# 1_0.net
KiCad netlist of a schematic drawn in EAGLE
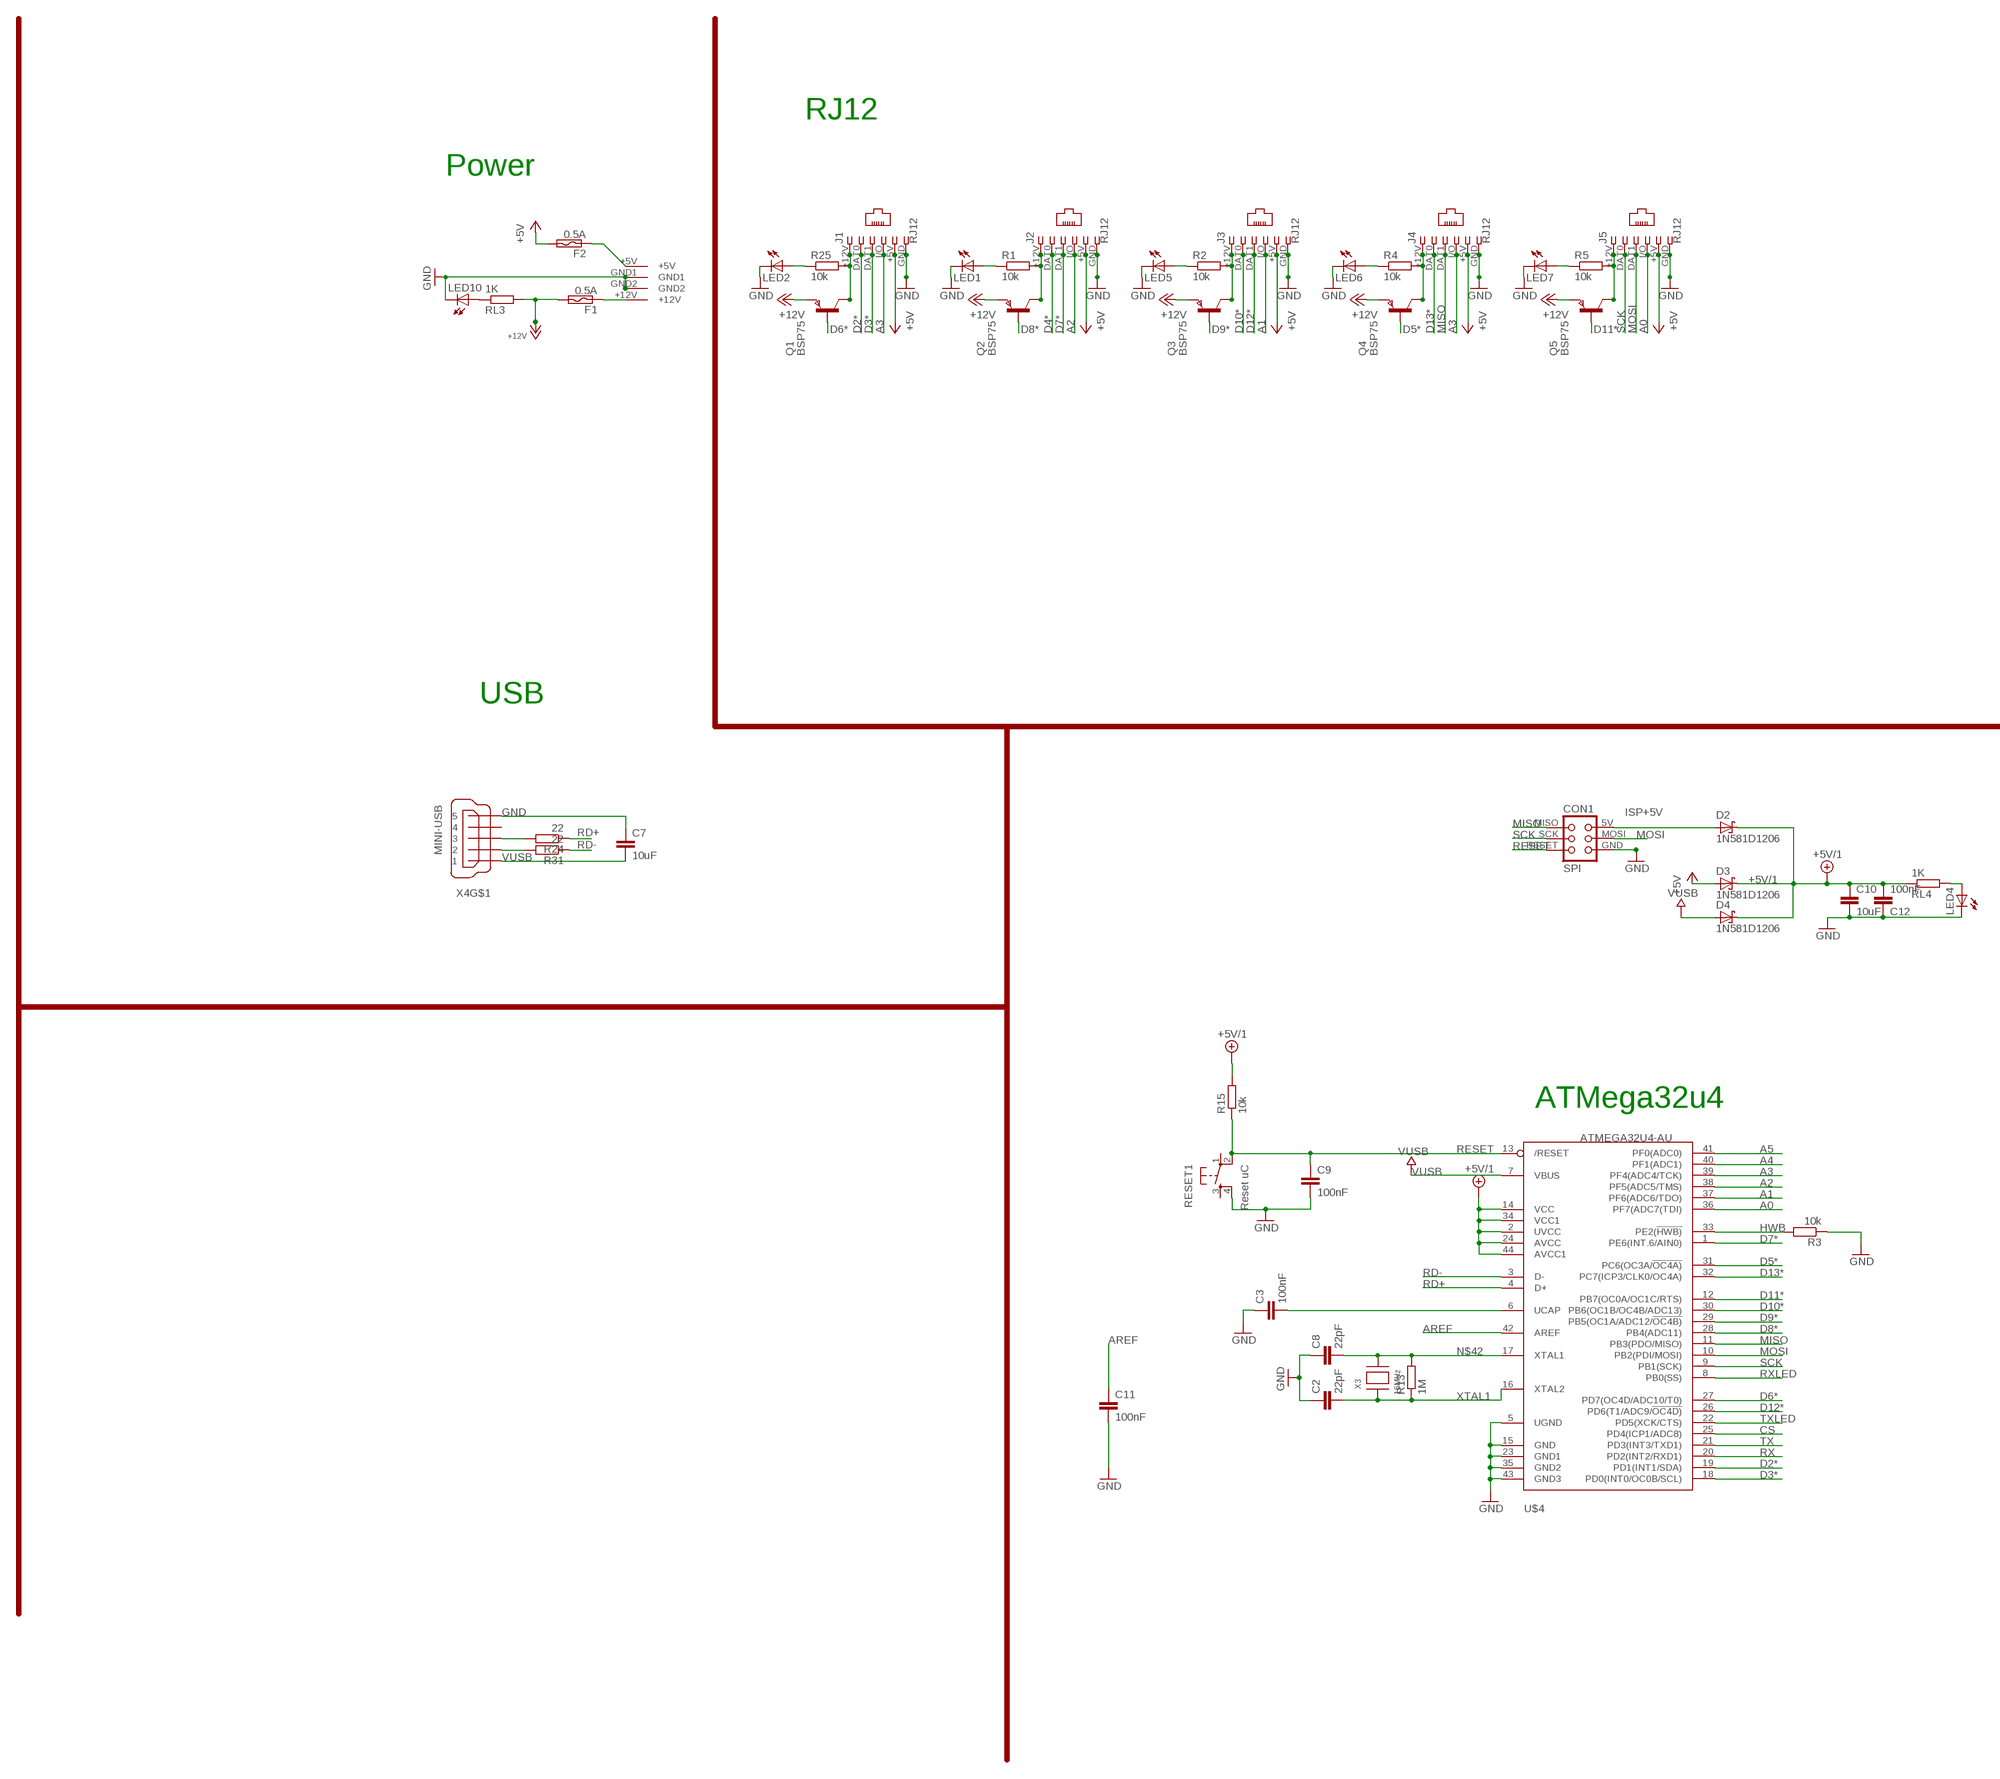
[diagram p0: schematic, sheet 1, part 1 of 2]
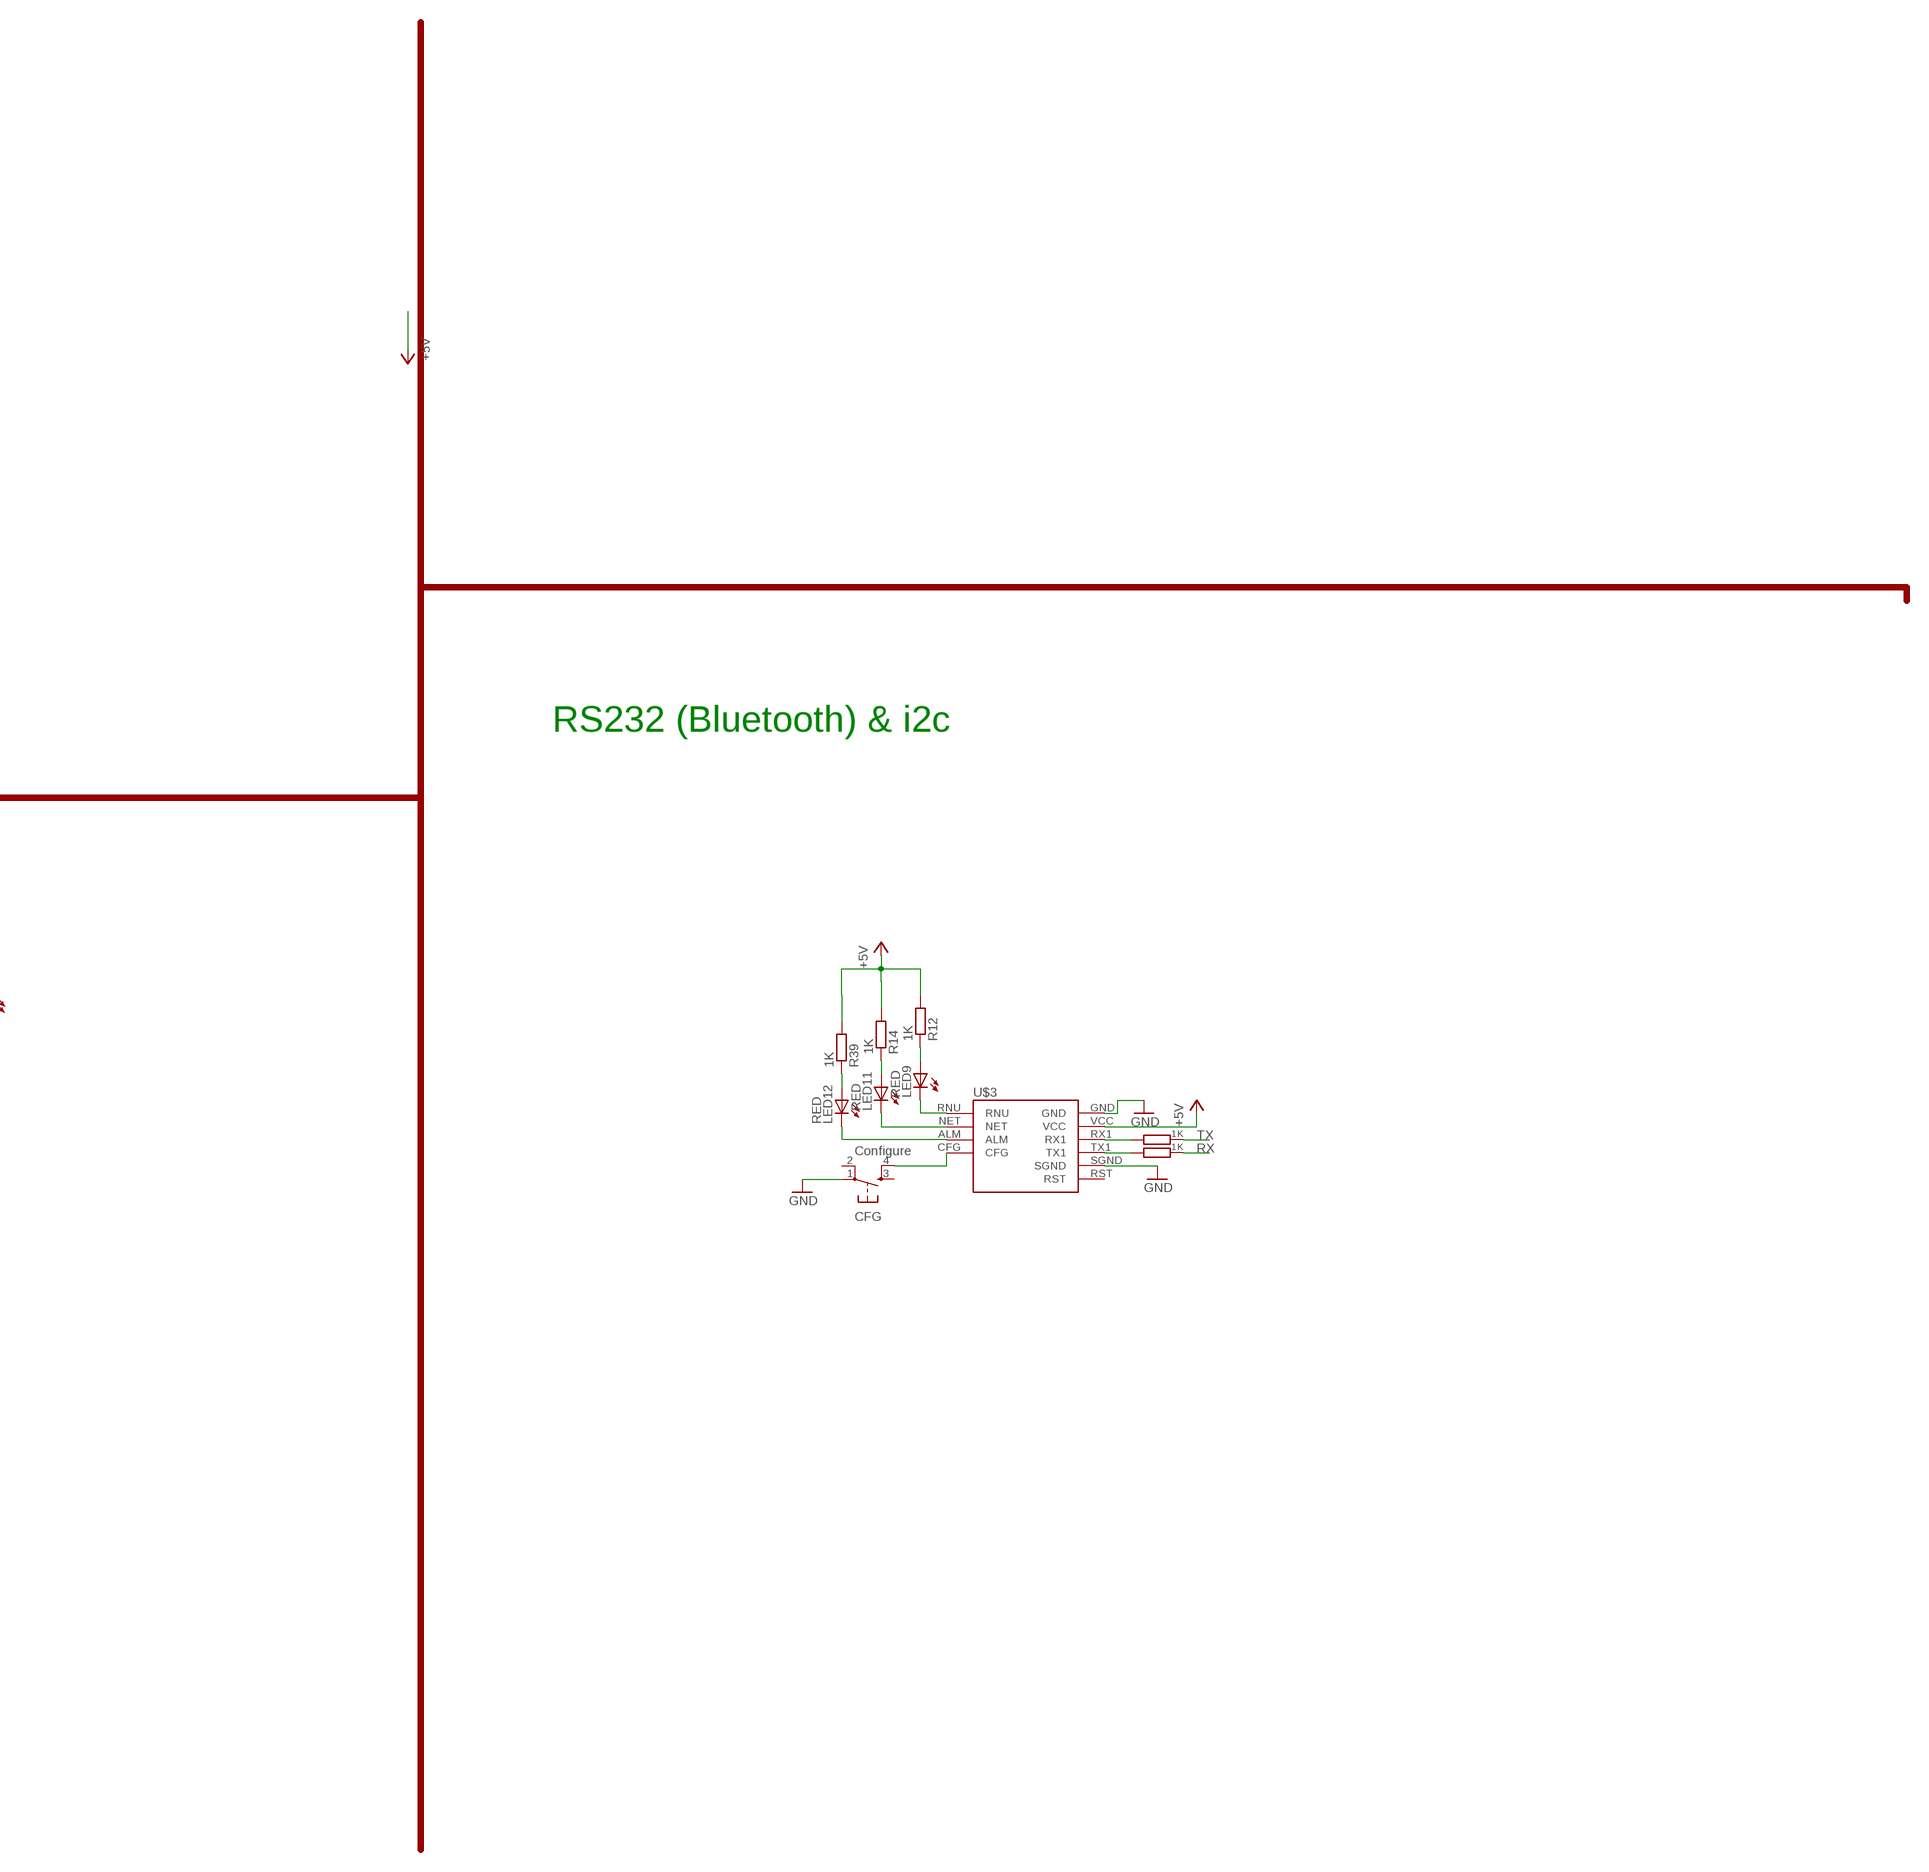
[diagram p1: schematic, sheet 1, part 2 of 2]

(export (version "E")
  (design (tool "Eeschema 10.0.6"))
  (components
    (comp (ref "C2")
      (value "22pF")
      (footprint "eagle-import:C1206")
      (libsource (lib "eagle-import") (part "C-EUC1206"))
    )
    (comp (ref "C3")
      (value "100nF")
      (footprint "eagle-import:C1206")
      (libsource (lib "eagle-import") (part "C-EUC1206"))
    )
    (comp (ref "C7")
      (value "10uF")
      (footprint "eagle-import:C1206")
      (libsource (lib "eagle-import") (part "C-EUC1206"))
    )
    (comp (ref "C8")
      (value "22pF")
      (footprint "eagle-import:C1206")
      (libsource (lib "eagle-import") (part "C-EUC1206"))
    )
    (comp (ref "C9")
      (value "100nF")
      (footprint "eagle-import:C1206")
      (libsource (lib "eagle-import") (part "C-EUC1206"))
    )
    (comp (ref "C10")
      (value "10uF")
      (footprint "eagle-import:C1206")
      (libsource (lib "eagle-import") (part "C-EUC1206"))
    )
    (comp (ref "C11")
      (value "100nF")
      (footprint "eagle-import:C1206")
      (libsource (lib "eagle-import") (part "C-EUC1206"))
    )
    (comp (ref "C12")
      (value "100nF")
      (footprint "eagle-import:C1206")
      (libsource (lib "eagle-import") (part "C-EUC1206"))
    )
    (comp (ref "CFG")
      (value "Configure")
      (footprint "eagle-import:TACTILE_SWITCH_SMD")
      (libsource (lib "eagle-import") (part "TAC_SWITCHSMD"))
    )
    (comp (ref "CON1")
      (value "SPI")
      (footprint "eagle-import:TC2030-MCP")
      (libsource (lib "eagle-import") (part "TINYISPTAG"))
    )
    (comp (ref "D2")
      (value "1N581D1206")
      (footprint "eagle-import:LED-1206")
      (libsource (lib "eagle-import") (part "1N581D1206"))
    )
    (comp (ref "D3")
      (value "1N581D1206")
      (footprint "eagle-import:LED-1206")
      (libsource (lib "eagle-import") (part "1N581D1206"))
    )
    (comp (ref "D4")
      (value "1N581D1206")
      (footprint "eagle-import:LED-1206")
      (libsource (lib "eagle-import") (part "1N581D1206"))
    )
    (comp (ref "F1")
      (value "0.5A")
      (footprint "eagle-import:C1812")
      (libsource (lib "eagle-import") (part "POLYSWITCHSMD1812"))
    )
    (comp (ref "F2")
      (value "0.5A")
      (footprint "eagle-import:C1812")
      (libsource (lib "eagle-import") (part "POLYSWITCHSMD1812"))
    )
    (comp (ref "J1")
      (value "RJ12")
      (footprint "eagle-import:RJ12-STRAIGHT-WIEGAND")
      (libsource (lib "eagle-import") (part "RJ12STR-WIEGAND"))
    )
    (comp (ref "J2")
      (value "RJ12")
      (footprint "eagle-import:RJ12-STRAIGHT-WIEGAND")
      (libsource (lib "eagle-import") (part "RJ12STR-WIEGAND"))
    )
    (comp (ref "J3")
      (value "RJ12")
      (footprint "eagle-import:RJ12-STRAIGHT-WIEGAND")
      (libsource (lib "eagle-import") (part "RJ12STR-WIEGAND"))
    )
    (comp (ref "J4")
      (value "RJ12")
      (footprint "eagle-import:RJ12-STRAIGHT-WIEGAND")
      (libsource (lib "eagle-import") (part "RJ12STR-WIEGAND"))
    )
    (comp (ref "J5")
      (value "RJ12")
      (footprint "eagle-import:RJ12-STRAIGHT-WIEGAND")
      (libsource (lib "eagle-import") (part "RJ12STR-WIEGAND"))
    )
    (comp (ref "LED1")
      (value "Blue")
      (footprint "eagle-import:LED3MM")
      (libsource (lib "eagle-import") (part "lpatiny_LED3MM"))
    )
    (comp (ref "LED2")
      (value "Blue")
      (footprint "eagle-import:LED3MM")
      (libsource (lib "eagle-import") (part "lpatiny_LED3MM"))
    )
    (comp (ref "LED4")
      (value "RED")
      (footprint "eagle-import:LED3MM")
      (libsource (lib "eagle-import") (part "lpatiny_LED3MM"))
    )
    (comp (ref "LED5")
      (value "Blue")
      (footprint "eagle-import:LED3MM")
      (libsource (lib "eagle-import") (part "lpatiny_LED3MM"))
    )
    (comp (ref "LED6")
      (value "Blue")
      (footprint "eagle-import:LED3MM")
      (libsource (lib "eagle-import") (part "lpatiny_LED3MM"))
    )
    (comp (ref "LED7")
      (value "Blue")
      (footprint "eagle-import:LED3MM")
      (libsource (lib "eagle-import") (part "lpatiny_LED3MM"))
    )
    (comp (ref "LED9")
      (value "RED")
      (footprint "eagle-import:CHIP-LED0805")
      (libsource (lib "eagle-import") (part "LEDCHIP-LED0805"))
    )
    (comp (ref "LED10")
      (value "RED")
      (footprint "eagle-import:LED3MM")
      (libsource (lib "eagle-import") (part "lpatiny_LED3MM"))
    )
    (comp (ref "LED11")
      (value "RED")
      (footprint "eagle-import:CHIP-LED0805")
      (libsource (lib "eagle-import") (part "LEDCHIP-LED0805"))
    )
    (comp (ref "LED12")
      (value "RED")
      (footprint "eagle-import:CHIP-LED0805")
      (libsource (lib "eagle-import") (part "LEDCHIP-LED0805"))
    )
    (comp (ref "Q1")
      (value "BSP75")
      (footprint "eagle-import:SOT223")
      (fields (field (name "MPN") "DJT4030P-13"))
      (libsource (lib "eagle-import") (part "PNPSOT223"))
    )
    (comp (ref "Q2")
      (value "BSP75")
      (footprint "eagle-import:SOT223")
      (fields (field (name "MPN") "DJT4030P-13"))
      (libsource (lib "eagle-import") (part "PNPSOT223"))
    )
    (comp (ref "Q3")
      (value "BSP75")
      (footprint "eagle-import:SOT223")
      (fields (field (name "MPN") "DJT4030P-13"))
      (libsource (lib "eagle-import") (part "PNPSOT223"))
    )
    (comp (ref "Q4")
      (value "BSP75")
      (footprint "eagle-import:SOT223")
      (fields (field (name "MPN") "DJT4030P-13"))
      (libsource (lib "eagle-import") (part "PNPSOT223"))
    )
    (comp (ref "Q5")
      (value "BSP75")
      (footprint "eagle-import:SOT223")
      (fields (field (name "MPN") "DJT4030P-13"))
      (libsource (lib "eagle-import") (part "PNPSOT223"))
    )
    (comp (ref "R1")
      (value "10k")
      (footprint "eagle-import:R0805")
      (libsource (lib "eagle-import") (part "R-EU_R0805"))
    )
    (comp (ref "R2")
      (value "10k")
      (footprint "eagle-import:R0805")
      (libsource (lib "eagle-import") (part "R-EU_R0805"))
    )
    (comp (ref "R3")
      (value "10k")
      (footprint "eagle-import:M0805")
      (libsource (lib "eagle-import") (part "resistor_R-EU_M0805"))
    )
    (comp (ref "R4")
      (value "10k")
      (footprint "eagle-import:R0805")
      (libsource (lib "eagle-import") (part "R-EU_R0805"))
    )
    (comp (ref "R5")
      (value "10k")
      (footprint "eagle-import:R0805")
      (libsource (lib "eagle-import") (part "R-EU_R0805"))
    )
    (comp (ref "R8")
      (value "1K")
      (footprint "eagle-import:R0805")
      (libsource (lib "eagle-import") (part "R-EU_R0805"))
    )
    (comp (ref "R11")
      (value "1K")
      (footprint "eagle-import:R0805")
      (libsource (lib "eagle-import") (part "R-EU_R0805"))
    )
    (comp (ref "R12")
      (value "1K")
      (footprint "eagle-import:R0805")
      (libsource (lib "eagle-import") (part "R-EU_R0805"))
    )
    (comp (ref "R13")
      (value "1M")
      (footprint "eagle-import:R1206")
      (libsource (lib "eagle-import") (part "R-EU_R1206"))
    )
    (comp (ref "R14")
      (value "1K")
      (footprint "eagle-import:R0805")
      (libsource (lib "eagle-import") (part "R-EU_R0805"))
    )
    (comp (ref "R15")
      (value "10k")
      (footprint "eagle-import:M0805")
      (libsource (lib "eagle-import") (part "resistor_R-EU_M0805"))
    )
    (comp (ref "R24")
      (value "22")
      (footprint "eagle-import:M1206")
      (libsource (lib "eagle-import") (part "resistor_R-EU_M1206"))
    )
    (comp (ref "R25")
      (value "10k")
      (footprint "eagle-import:R0805")
      (libsource (lib "eagle-import") (part "R-EU_R0805"))
    )
    (comp (ref "R31")
      (value "22")
      (footprint "eagle-import:M1206")
      (libsource (lib "eagle-import") (part "resistor_R-EU_M1206"))
    )
    (comp (ref "R39")
      (value "1K")
      (footprint "eagle-import:R0805")
      (libsource (lib "eagle-import") (part "R-EU_R0805"))
    )
    (comp (ref "RESET1")
      (value "Reset uC")
      (footprint "eagle-import:TACTILE_SWITCH_SMD")
      (libsource (lib "eagle-import") (part "TAC_SWITCHSMD"))
    )
    (comp (ref "RL3")
      (value "1K")
      (footprint "eagle-import:R0805")
      (libsource (lib "eagle-import") (part "R-EU_R0805"))
    )
    (comp (ref "RL4")
      (value "1K")
      (footprint "eagle-import:R0805")
      (libsource (lib "eagle-import") (part "resistor_R-EU_R0805"))
    )
    (comp (ref "U$3")
      (value "SZ05-ZIGBEE")
      (footprint "eagle-import:SZ05-ZIGBEE")
      (libsource (lib "eagle-import") (part "SZ05-ZIGBEE"))
    )
    (comp (ref "U$4")
      (value "ATMEGA32U4-AU")
      (footprint "eagle-import:TQFP44")
      (libsource (lib "eagle-import") (part "ATMEGA32U4-AU"))
    )
    (comp (ref "U$6")
      (value "KPJX-4S-S")
      (footprint "eagle-import:KPJX-4S-S")
      (libsource (lib "eagle-import") (part "KPJX-4S-S"))
    )
    (comp (ref "X3")
      (value "16MHz")
      (footprint "eagle-import:NX6035")
      (libsource (lib "eagle-import") (part "XTALNX6035"))
    )
    (comp (ref "X4")
      (value "MINI-USB")
      (footprint "eagle-import:32005-201")
      (libsource (lib "eagle-import") (part "MINI-USB-SCHIELD-32005-201"))
    )
  )
  (nets
    (net (code "1") (name "+5V") (class "Default")
      (node (ref "D3") (pin "A") (pinfunction "A_A") (pintype "passive"))
      (node (ref "F2") (pin "2") (pinfunction "2_2") (pintype "passive"))
      (node (ref "J1") (pin "+5V") (pinfunction "5_+5V") (pintype "bidirectional"))
      (node (ref "J2") (pin "+5V") (pinfunction "5_+5V") (pintype "bidirectional"))
      (node (ref "J3") (pin "+5V") (pinfunction "5_+5V") (pintype "bidirectional"))
      (node (ref "J4") (pin "+5V") (pinfunction "5_+5V") (pintype "bidirectional"))
      (node (ref "J5") (pin "+5V") (pinfunction "5_+5V") (pintype "bidirectional"))
      (node (ref "R12") (pin "2") (pinfunction "2_2") (pintype "passive"))
      (node (ref "R14") (pin "2") (pinfunction "2_2") (pintype "passive"))
      (node (ref "R39") (pin "2") (pinfunction "2_2") (pintype "passive"))
      (node (ref "U$3") (pin "VCC") (pinfunction "VCC_VCC") (pintype "bidirectional"))
    )
    (net (code "2") (name "+5V{slash}1") (class "Default")
      (node (ref "C10") (pin "1") (pinfunction "1_1") (pintype "passive"))
      (node (ref "C12") (pin "2") (pinfunction "2_2") (pintype "passive"))
      (node (ref "D2") (pin "C") (pinfunction "C_C") (pintype "passive"))
      (node (ref "D3") (pin "C") (pinfunction "C_C") (pintype "passive"))
      (node (ref "D4") (pin "C") (pinfunction "C_C") (pintype "passive"))
      (node (ref "R15") (pin "2") (pinfunction "2_2") (pintype "passive"))
      (node (ref "RL4") (pin "1") (pinfunction "1_1") (pintype "passive"))
      (node (ref "U$4") (pin "14") (pinfunction "VCC_14") (pintype "bidirectional"))
      (node (ref "U$4") (pin "2") (pinfunction "UVCC_2") (pintype "bidirectional"))
      (node (ref "U$4") (pin "24") (pinfunction "AVCC_24") (pintype "bidirectional"))
      (node (ref "U$4") (pin "34") (pinfunction "VCC1_34") (pintype "bidirectional"))
      (node (ref "U$4") (pin "44") (pinfunction "AVCC1_44") (pintype "bidirectional"))
    )
    (net (code "3") (name "+12V") (class "Default")
      (node (ref "F1") (pin "2") (pinfunction "2_2") (pintype "passive"))
      (node (ref "Q1") (pin "3") (pinfunction "E_3") (pintype "passive"))
      (node (ref "Q2") (pin "3") (pinfunction "E_3") (pintype "passive"))
      (node (ref "Q3") (pin "3") (pinfunction "E_3") (pintype "passive"))
      (node (ref "Q4") (pin "3") (pinfunction "E_3") (pintype "passive"))
      (node (ref "Q5") (pin "3") (pinfunction "E_3") (pintype "passive"))
      (node (ref "RL3") (pin "2") (pinfunction "2_2") (pintype "passive"))
    )
    (net (code "4") (name "/A0") (class "Default")
      (node (ref "J5") (pin "I/O") (pinfunction "4_I/O") (pintype "bidirectional"))
      (node (ref "U$4") (pin "36") (pinfunction "PF7(ADC7(TDI)_36") (pintype "bidirectional"))
    )
    (net (code "5") (name "/A1") (class "Default")
      (node (ref "J3") (pin "I/O") (pinfunction "4_I/O") (pintype "bidirectional"))
      (node (ref "U$4") (pin "37") (pinfunction "PF6(ADC6/TDO)_37") (pintype "bidirectional"))
    )
    (net (code "6") (name "/A2") (class "Default")
      (node (ref "J2") (pin "I/O") (pinfunction "4_I/O") (pintype "bidirectional"))
      (node (ref "U$4") (pin "38") (pinfunction "PF5(ADC5/TMS)_38") (pintype "bidirectional"))
    )
    (net (code "7") (name "/A3") (class "Default")
      (node (ref "J1") (pin "I/O") (pinfunction "4_I/O") (pintype "bidirectional"))
      (node (ref "J4") (pin "I/O") (pinfunction "4_I/O") (pintype "bidirectional"))
      (node (ref "U$4") (pin "39") (pinfunction "PF4(ADC4/TCK)_39") (pintype "bidirectional"))
    )
    (net (code "8") (name "/A4") (class "Default")
      (node (ref "U$4") (pin "40") (pinfunction "PF1(ADC1)_40") (pintype "bidirectional"))
    )
    (net (code "9") (name "/A5") (class "Default")
      (node (ref "U$4") (pin "41") (pinfunction "PF0(ADC0)_41") (pintype "bidirectional"))
    )
    (net (code "10") (name "/AREF") (class "Default")
      (node (ref "C11") (pin "1") (pinfunction "1_1") (pintype "passive"))
      (node (ref "U$4") (pin "42") (pinfunction "AREF_42") (pintype "bidirectional"))
    )
    (net (code "11") (name "/CS") (class "Default")
      (node (ref "U$4") (pin "25") (pinfunction "PD4(ICP1/ADC8)_25") (pintype "bidirectional"))
    )
    (net (code "12") (name "/D2*") (class "Default")
      (node (ref "J1") (pin "DAT0") (pinfunction "2_DAT0") (pintype "bidirectional"))
      (node (ref "U$4") (pin "19") (pinfunction "PD1(INT1/SDA)_19") (pintype "bidirectional"))
    )
    (net (code "13") (name "/D3*") (class "Default")
      (node (ref "J1") (pin "DAT1") (pinfunction "3_DAT1") (pintype "bidirectional"))
      (node (ref "U$4") (pin "18") (pinfunction "PD0(INT0/OC0B/SCL)_18") (pintype "bidirectional"))
    )
    (net (code "14") (name "/D4*") (class "Default")
      (node (ref "J2") (pin "DAT0") (pinfunction "2_DAT0") (pintype "bidirectional"))
    )
    (net (code "15") (name "/D5*") (class "Default")
      (node (ref "Q4") (pin "1") (pinfunction "B_1") (pintype "passive"))
      (node (ref "U$4") (pin "31") (pinfunction "PC6(OC3A/~{OC4A})_31") (pintype "bidirectional"))
    )
    (net (code "16") (name "/D6*") (class "Default")
      (node (ref "Q1") (pin "1") (pinfunction "B_1") (pintype "passive"))
      (node (ref "U$4") (pin "27") (pinfunction "PD7(OC4D/ADC10/T0)_27") (pintype "bidirectional"))
    )
    (net (code "17") (name "/D7*") (class "Default")
      (node (ref "J2") (pin "DAT1") (pinfunction "3_DAT1") (pintype "bidirectional"))
      (node (ref "U$4") (pin "1") (pinfunction "PE6(INT.6/AIN0)_1") (pintype "bidirectional"))
    )
    (net (code "18") (name "/D8*") (class "Default")
      (node (ref "Q2") (pin "1") (pinfunction "B_1") (pintype "passive"))
      (node (ref "U$4") (pin "28") (pinfunction "PB4(ADC11)_28") (pintype "bidirectional"))
    )
    (net (code "19") (name "/D9*") (class "Default")
      (node (ref "Q3") (pin "1") (pinfunction "B_1") (pintype "passive"))
      (node (ref "U$4") (pin "29") (pinfunction "PB5(OC1A/ADC12/~{OC4B})_29") (pintype "bidirectional"))
    )
    (net (code "20") (name "/D10*") (class "Default")
      (node (ref "J3") (pin "DAT0") (pinfunction "2_DAT0") (pintype "bidirectional"))
      (node (ref "U$4") (pin "30") (pinfunction "PB6(OC1B/OC4B/ADC13)_30") (pintype "bidirectional"))
    )
    (net (code "21") (name "/D11*") (class "Default")
      (node (ref "Q5") (pin "1") (pinfunction "B_1") (pintype "passive"))
      (node (ref "U$4") (pin "12") (pinfunction "PB7(OC0A/OC1C/RTS)_12") (pintype "bidirectional"))
    )
    (net (code "22") (name "/D12*") (class "Default")
      (node (ref "J3") (pin "DAT1") (pinfunction "3_DAT1") (pintype "bidirectional"))
      (node (ref "U$4") (pin "26") (pinfunction "PD6(T1/ADC9/~{OC4D})_26") (pintype "bidirectional"))
    )
    (net (code "23") (name "/D13*") (class "Default")
      (node (ref "J4") (pin "DAT0") (pinfunction "2_DAT0") (pintype "bidirectional"))
      (node (ref "U$4") (pin "32") (pinfunction "PC7(ICP3/CLK0/OC4A)_32") (pintype "bidirectional"))
    )
    (net (code "24") (name "/HWB") (class "Default")
      (node (ref "R3") (pin "2") (pinfunction "2_2") (pintype "passive"))
      (node (ref "U$4") (pin "33") (pinfunction "PE2(~{HWB})_33") (pintype "bidirectional"))
    )
    (net (code "25") (name "/ISP+5V") (class "Default")
      (node (ref "CON1") (pin "5V") (pinfunction "VCC_5V") (pintype "passive"))
      (node (ref "D2") (pin "A") (pinfunction "A_A") (pintype "passive"))
    )
    (net (code "26") (name "/MISO") (class "Default")
      (node (ref "CON1") (pin "MISO") (pinfunction "MISO_MISO") (pintype "passive"))
      (node (ref "J4") (pin "DAT1") (pinfunction "3_DAT1") (pintype "bidirectional"))
      (node (ref "U$4") (pin "11") (pinfunction "PB3(PDO/MISO)_11") (pintype "bidirectional"))
    )
    (net (code "27") (name "/MOSI") (class "Default")
      (node (ref "CON1") (pin "MOSI") (pinfunction "MOSI_MOSI") (pintype "passive"))
      (node (ref "J5") (pin "DAT1") (pinfunction "3_DAT1") (pintype "bidirectional"))
      (node (ref "U$4") (pin "10") (pinfunction "PB2(PDI/MOSI)_10") (pintype "bidirectional"))
    )
    (net (code "28") (name "/N$42") (class "Default")
      (node (ref "C8") (pin "2") (pinfunction "2_2") (pintype "passive"))
      (node (ref "R13") (pin "2") (pinfunction "2_2") (pintype "passive"))
      (node (ref "U$4") (pin "17") (pinfunction "XTAL1_17") (pintype "bidirectional"))
      (node (ref "X3") (pin "P$2") (pinfunction "P$2_P$2") (pintype "bidirectional"))
    )
    (net (code "29") (name "/RD+") (class "Default")
      (node (ref "R24") (pin "1") (pinfunction "1_1") (pintype "passive"))
      (node (ref "U$4") (pin "4") (pinfunction "D+_4") (pintype "bidirectional"))
    )
    (net (code "30") (name "/RD-") (class "Default")
      (node (ref "R31") (pin "1") (pinfunction "1_1") (pintype "passive"))
      (node (ref "U$4") (pin "3") (pinfunction "D-_3") (pintype "bidirectional"))
    )
    (net (code "31") (name "/RESET") (class "Default")
      (node (ref "C9") (pin "1") (pinfunction "1_1") (pintype "passive"))
      (node (ref "CON1") (pin "RESET") (pinfunction "RESET_RESET") (pintype "passive"))
      (node (ref "R15") (pin "1") (pinfunction "1_1") (pintype "passive"))
      (node (ref "RESET1") (pin "2") (pinfunction "2_2") (pintype "passive"))
      (node (ref "U$4") (pin "13") (pinfunction "/RESET_13") (pintype "bidirectional"))
    )
    (net (code "32") (name "/RX") (class "Default")
      (node (ref "R8") (pin "1") (pinfunction "1_1") (pintype "passive"))
      (node (ref "U$4") (pin "20") (pinfunction "PD2(INT2/RXD1)_20") (pintype "bidirectional"))
    )
    (net (code "33") (name "/RXLED") (class "Default")
      (node (ref "U$4") (pin "8") (pinfunction "PB0(SS)_8") (pintype "bidirectional"))
    )
    (net (code "34") (name "/SCK") (class "Default")
      (node (ref "CON1") (pin "SCK") (pinfunction "SCK_SCK") (pintype "passive"))
      (node (ref "J5") (pin "DAT0") (pinfunction "2_DAT0") (pintype "bidirectional"))
      (node (ref "U$4") (pin "9") (pinfunction "PB1(SCK)_9") (pintype "bidirectional"))
    )
    (net (code "35") (name "/TX") (class "Default")
      (node (ref "R11") (pin "1") (pinfunction "1_1") (pintype "passive"))
      (node (ref "U$4") (pin "21") (pinfunction "PD3(INT3/TXD1)_21") (pintype "bidirectional"))
    )
    (net (code "36") (name "/TXLED") (class "Default")
      (node (ref "U$4") (pin "22") (pinfunction "PD5(XCK/CTS)_22") (pintype "bidirectional"))
    )
    (net (code "37") (name "/XTAL1") (class "Default")
      (node (ref "C2") (pin "2") (pinfunction "2_2") (pintype "passive"))
      (node (ref "R13") (pin "1") (pinfunction "1_1") (pintype "passive"))
      (node (ref "U$4") (pin "16") (pinfunction "XTAL2_16") (pintype "bidirectional"))
      (node (ref "X3") (pin "P$1") (pinfunction "P$1_P$1") (pintype "bidirectional"))
    )
    (net (code "38") (name "GND") (class "Default")
      (node (ref "C10") (pin "2") (pinfunction "2_2") (pintype "passive"))
      (node (ref "C11") (pin "2") (pinfunction "2_2") (pintype "passive"))
      (node (ref "C12") (pin "1") (pinfunction "1_1") (pintype "passive"))
      (node (ref "C2") (pin "1") (pinfunction "1_1") (pintype "passive"))
      (node (ref "C3") (pin "1") (pinfunction "1_1") (pintype "passive"))
      (node (ref "C7") (pin "1") (pinfunction "1_1") (pintype "passive"))
      (node (ref "C8") (pin "1") (pinfunction "1_1") (pintype "passive"))
      (node (ref "C9") (pin "2") (pinfunction "2_2") (pintype "passive"))
      (node (ref "CFG") (pin "1") (pinfunction "1_1") (pintype "passive"))
      (node (ref "CON1") (pin "GND") (pinfunction "GND_GND") (pintype "passive"))
      (node (ref "J1") (pin "GND") (pinfunction "6_GND") (pintype "bidirectional"))
      (node (ref "J2") (pin "GND") (pinfunction "6_GND") (pintype "bidirectional"))
      (node (ref "J3") (pin "GND") (pinfunction "6_GND") (pintype "bidirectional"))
      (node (ref "J4") (pin "GND") (pinfunction "6_GND") (pintype "bidirectional"))
      (node (ref "J5") (pin "GND") (pinfunction "6_GND") (pintype "bidirectional"))
      (node (ref "LED1") (pin "K") (pinfunction "C_K") (pintype "passive"))
      (node (ref "LED10") (pin "K") (pinfunction "C_K") (pintype "passive"))
      (node (ref "LED2") (pin "K") (pinfunction "C_K") (pintype "passive"))
      (node (ref "LED4") (pin "K") (pinfunction "C_K") (pintype "passive"))
      (node (ref "LED5") (pin "K") (pinfunction "C_K") (pintype "passive"))
      (node (ref "LED6") (pin "K") (pinfunction "C_K") (pintype "passive"))
      (node (ref "LED7") (pin "K") (pinfunction "C_K") (pintype "passive"))
      (node (ref "R3") (pin "1") (pinfunction "1_1") (pintype "passive"))
      (node (ref "RESET1") (pin "4") (pinfunction "4_4") (pintype "passive"))
      (node (ref "U$3") (pin "GND") (pinfunction "GND_GND") (pintype "bidirectional"))
      (node (ref "U$3") (pin "SGND") (pinfunction "SGND_SGND") (pintype "bidirectional"))
      (node (ref "U$4") (pin "15") (pinfunction "GND_15") (pintype "bidirectional"))
      (node (ref "U$4") (pin "23") (pinfunction "GND1_23") (pintype "bidirectional"))
      (node (ref "U$4") (pin "35") (pinfunction "GND2_35") (pintype "bidirectional"))
      (node (ref "U$4") (pin "43") (pinfunction "GND3_43") (pintype "bidirectional"))
      (node (ref "U$4") (pin "5") (pinfunction "UGND_5") (pintype "bidirectional"))
      (node (ref "U$6") (pin "GND1") (pinfunction "GND1_GND1") (pintype "input"))
      (node (ref "U$6") (pin "GND2") (pinfunction "GND2_GND2") (pintype "input"))
      (node (ref "X4") (pin "5") (pinfunction "5_5") (pintype "passive"))
    )
    (net (code "39") (name "Net-(CFG-Pad4)") (class "Default")
      (node (ref "CFG") (pin "4") (pinfunction "4_4") (pintype "passive"))
      (node (ref "U$3") (pin "CFG") (pinfunction "CFG_CFG") (pintype "bidirectional"))
    )
    (net (code "40") (name "Net-(F1-Pad1)") (class "Default")
      (node (ref "F1") (pin "1") (pinfunction "1_1") (pintype "passive"))
      (node (ref "U$6") (pin "+12V") (pinfunction "+12V_+12V") (pintype "power_in"))
    )
    (net (code "41") (name "Net-(F2-Pad1)") (class "Default")
      (node (ref "F2") (pin "1") (pinfunction "1_1") (pintype "passive"))
      (node (ref "U$6") (pin "+5V") (pinfunction "+5V_+5V") (pintype "power_in"))
    )
    (net (code "42") (name "Net-(J1-1)") (class "Default")
      (node (ref "J1") (pin "+12V") (pinfunction "1_+12V") (pintype "bidirectional"))
      (node (ref "Q1") (pin "2") (pinfunction "C_2") (pintype "passive"))
      (node (ref "Q1") (pin "4") (pinfunction "C_4") (pintype "passive"))
      (node (ref "R25") (pin "2") (pinfunction "2_2") (pintype "passive"))
    )
    (net (code "43") (name "Net-(J2-1)") (class "Default")
      (node (ref "J2") (pin "+12V") (pinfunction "1_+12V") (pintype "bidirectional"))
      (node (ref "Q2") (pin "2") (pinfunction "C_2") (pintype "passive"))
      (node (ref "Q2") (pin "4") (pinfunction "C_4") (pintype "passive"))
      (node (ref "R1") (pin "2") (pinfunction "2_2") (pintype "passive"))
    )
    (net (code "44") (name "Net-(J3-1)") (class "Default")
      (node (ref "J3") (pin "+12V") (pinfunction "1_+12V") (pintype "bidirectional"))
      (node (ref "Q3") (pin "2") (pinfunction "C_2") (pintype "passive"))
      (node (ref "Q3") (pin "4") (pinfunction "C_4") (pintype "passive"))
      (node (ref "R2") (pin "2") (pinfunction "2_2") (pintype "passive"))
    )
    (net (code "45") (name "Net-(J4-1)") (class "Default")
      (node (ref "J4") (pin "+12V") (pinfunction "1_+12V") (pintype "bidirectional"))
      (node (ref "Q4") (pin "2") (pinfunction "C_2") (pintype "passive"))
      (node (ref "Q4") (pin "4") (pinfunction "C_4") (pintype "passive"))
      (node (ref "R4") (pin "2") (pinfunction "2_2") (pintype "passive"))
    )
    (net (code "46") (name "Net-(J5-1)") (class "Default")
      (node (ref "J5") (pin "+12V") (pinfunction "1_+12V") (pintype "bidirectional"))
      (node (ref "Q5") (pin "2") (pinfunction "C_2") (pintype "passive"))
      (node (ref "Q5") (pin "4") (pinfunction "C_4") (pintype "passive"))
      (node (ref "R5") (pin "2") (pinfunction "2_2") (pintype "passive"))
    )
    (net (code "47") (name "Net-(LED1-PadA)") (class "Default")
      (node (ref "LED1") (pin "A") (pinfunction "A_A") (pintype "passive"))
      (node (ref "R1") (pin "1") (pinfunction "1_1") (pintype "passive"))
    )
    (net (code "48") (name "Net-(LED2-PadA)") (class "Default")
      (node (ref "LED2") (pin "A") (pinfunction "A_A") (pintype "passive"))
      (node (ref "R25") (pin "1") (pinfunction "1_1") (pintype "passive"))
    )
    (net (code "49") (name "Net-(LED4-PadA)") (class "Default")
      (node (ref "LED4") (pin "A") (pinfunction "A_A") (pintype "passive"))
      (node (ref "RL4") (pin "2") (pinfunction "2_2") (pintype "passive"))
    )
    (net (code "50") (name "Net-(LED5-PadA)") (class "Default")
      (node (ref "LED5") (pin "A") (pinfunction "A_A") (pintype "passive"))
      (node (ref "R2") (pin "1") (pinfunction "1_1") (pintype "passive"))
    )
    (net (code "51") (name "Net-(LED6-PadA)") (class "Default")
      (node (ref "LED6") (pin "A") (pinfunction "A_A") (pintype "passive"))
      (node (ref "R4") (pin "1") (pinfunction "1_1") (pintype "passive"))
    )
    (net (code "52") (name "Net-(LED7-PadA)") (class "Default")
      (node (ref "LED7") (pin "A") (pinfunction "A_A") (pintype "passive"))
      (node (ref "R5") (pin "1") (pinfunction "1_1") (pintype "passive"))
    )
    (net (code "53") (name "Net-(LED9-PadA)") (class "Default")
      (node (ref "LED9") (pin "A") (pinfunction "A_A") (pintype "passive"))
      (node (ref "R12") (pin "1") (pinfunction "1_1") (pintype "passive"))
    )
    (net (code "54") (name "Net-(LED9-PadC)") (class "Default")
      (node (ref "LED9") (pin "C") (pinfunction "C_C") (pintype "passive"))
      (node (ref "U$3") (pin "RNU") (pinfunction "RNU_RNU") (pintype "bidirectional"))
    )
    (net (code "55") (name "Net-(LED10-PadA)") (class "Default")
      (node (ref "LED10") (pin "A") (pinfunction "A_A") (pintype "passive"))
      (node (ref "RL3") (pin "1") (pinfunction "1_1") (pintype "passive"))
    )
    (net (code "56") (name "Net-(LED11-PadA)") (class "Default")
      (node (ref "LED11") (pin "A") (pinfunction "A_A") (pintype "passive"))
      (node (ref "R14") (pin "1") (pinfunction "1_1") (pintype "passive"))
    )
    (net (code "57") (name "Net-(LED11-PadC)") (class "Default")
      (node (ref "LED11") (pin "C") (pinfunction "C_C") (pintype "passive"))
      (node (ref "U$3") (pin "NET") (pinfunction "NET_NET") (pintype "bidirectional"))
    )
    (net (code "58") (name "Net-(LED12-PadA)") (class "Default")
      (node (ref "LED12") (pin "A") (pinfunction "A_A") (pintype "passive"))
      (node (ref "R39") (pin "1") (pinfunction "1_1") (pintype "passive"))
    )
    (net (code "59") (name "Net-(LED12-PadC)") (class "Default")
      (node (ref "LED12") (pin "C") (pinfunction "C_C") (pintype "passive"))
      (node (ref "U$3") (pin "ALM") (pinfunction "ALM_ALM") (pintype "bidirectional"))
    )
    (net (code "60") (name "Net-(R8-Pad2)") (class "Default")
      (node (ref "R8") (pin "2") (pinfunction "2_2") (pintype "passive"))
      (node (ref "U$3") (pin "TX1") (pinfunction "TX1_TX1") (pintype "bidirectional"))
    )
    (net (code "61") (name "Net-(R11-Pad2)") (class "Default")
      (node (ref "R11") (pin "2") (pinfunction "2_2") (pintype "passive"))
      (node (ref "U$3") (pin "RX1") (pinfunction "RX1_RX1") (pintype "bidirectional"))
    )
    (net (code "62") (name "Net-(R24-Pad2)") (class "Default")
      (node (ref "R24") (pin "2") (pinfunction "2_2") (pintype "passive"))
      (node (ref "X4") (pin "3") (pinfunction "3_3") (pintype "passive"))
    )
    (net (code "63") (name "Net-(R31-Pad2)") (class "Default")
      (node (ref "R31") (pin "2") (pinfunction "2_2") (pintype "passive"))
      (node (ref "X4") (pin "2") (pinfunction "2_2") (pintype "passive"))
    )
    (net (code "64") (name "Net-(U$4-UCAP)") (class "Default")
      (node (ref "C3") (pin "2") (pinfunction "2_2") (pintype "passive"))
      (node (ref "U$4") (pin "6") (pinfunction "UCAP_6") (pintype "bidirectional"))
    )
    (net (code "65") (name "VUSB") (class "Default")
      (node (ref "C7") (pin "2") (pinfunction "2_2") (pintype "passive"))
      (node (ref "D4") (pin "A") (pinfunction "A_A") (pintype "passive"))
      (node (ref "U$4") (pin "7") (pinfunction "VBUS_7") (pintype "bidirectional"))
      (node (ref "X4") (pin "1") (pinfunction "1_1") (pintype "passive"))
    )
    (net (code "66") (name "unconnected-(CFG-Pad2)") (class "Default")
      (node (ref "CFG") (pin "2") (pinfunction "2_2") (pintype "passive"))
    )
    (net (code "67") (name "unconnected-(CFG-Pad3)") (class "Default")
      (node (ref "CFG") (pin "3") (pinfunction "3_3") (pintype "passive"))
    )
    (net (code "68") (name "unconnected-(RESET1-Pad1)") (class "Default")
      (node (ref "RESET1") (pin "1") (pinfunction "1_1") (pintype "passive"))
    )
    (net (code "69") (name "unconnected-(RESET1-Pad3)") (class "Default")
      (node (ref "RESET1") (pin "3") (pinfunction "3_3") (pintype "passive"))
    )
    (net (code "70") (name "unconnected-(U$3-PadRST)") (class "Default")
      (node (ref "U$3") (pin "RST") (pinfunction "RST_RST") (pintype "bidirectional"))
    )
    (net (code "71") (name "unconnected-(X4-Pad4)") (class "Default")
      (node (ref "X4") (pin "4") (pinfunction "4_4") (pintype "passive"))
    )
  )
)
